# 1-Schematic_Payload_Controller.net
KiCad netlist of a schematic drawn in EasyEDA
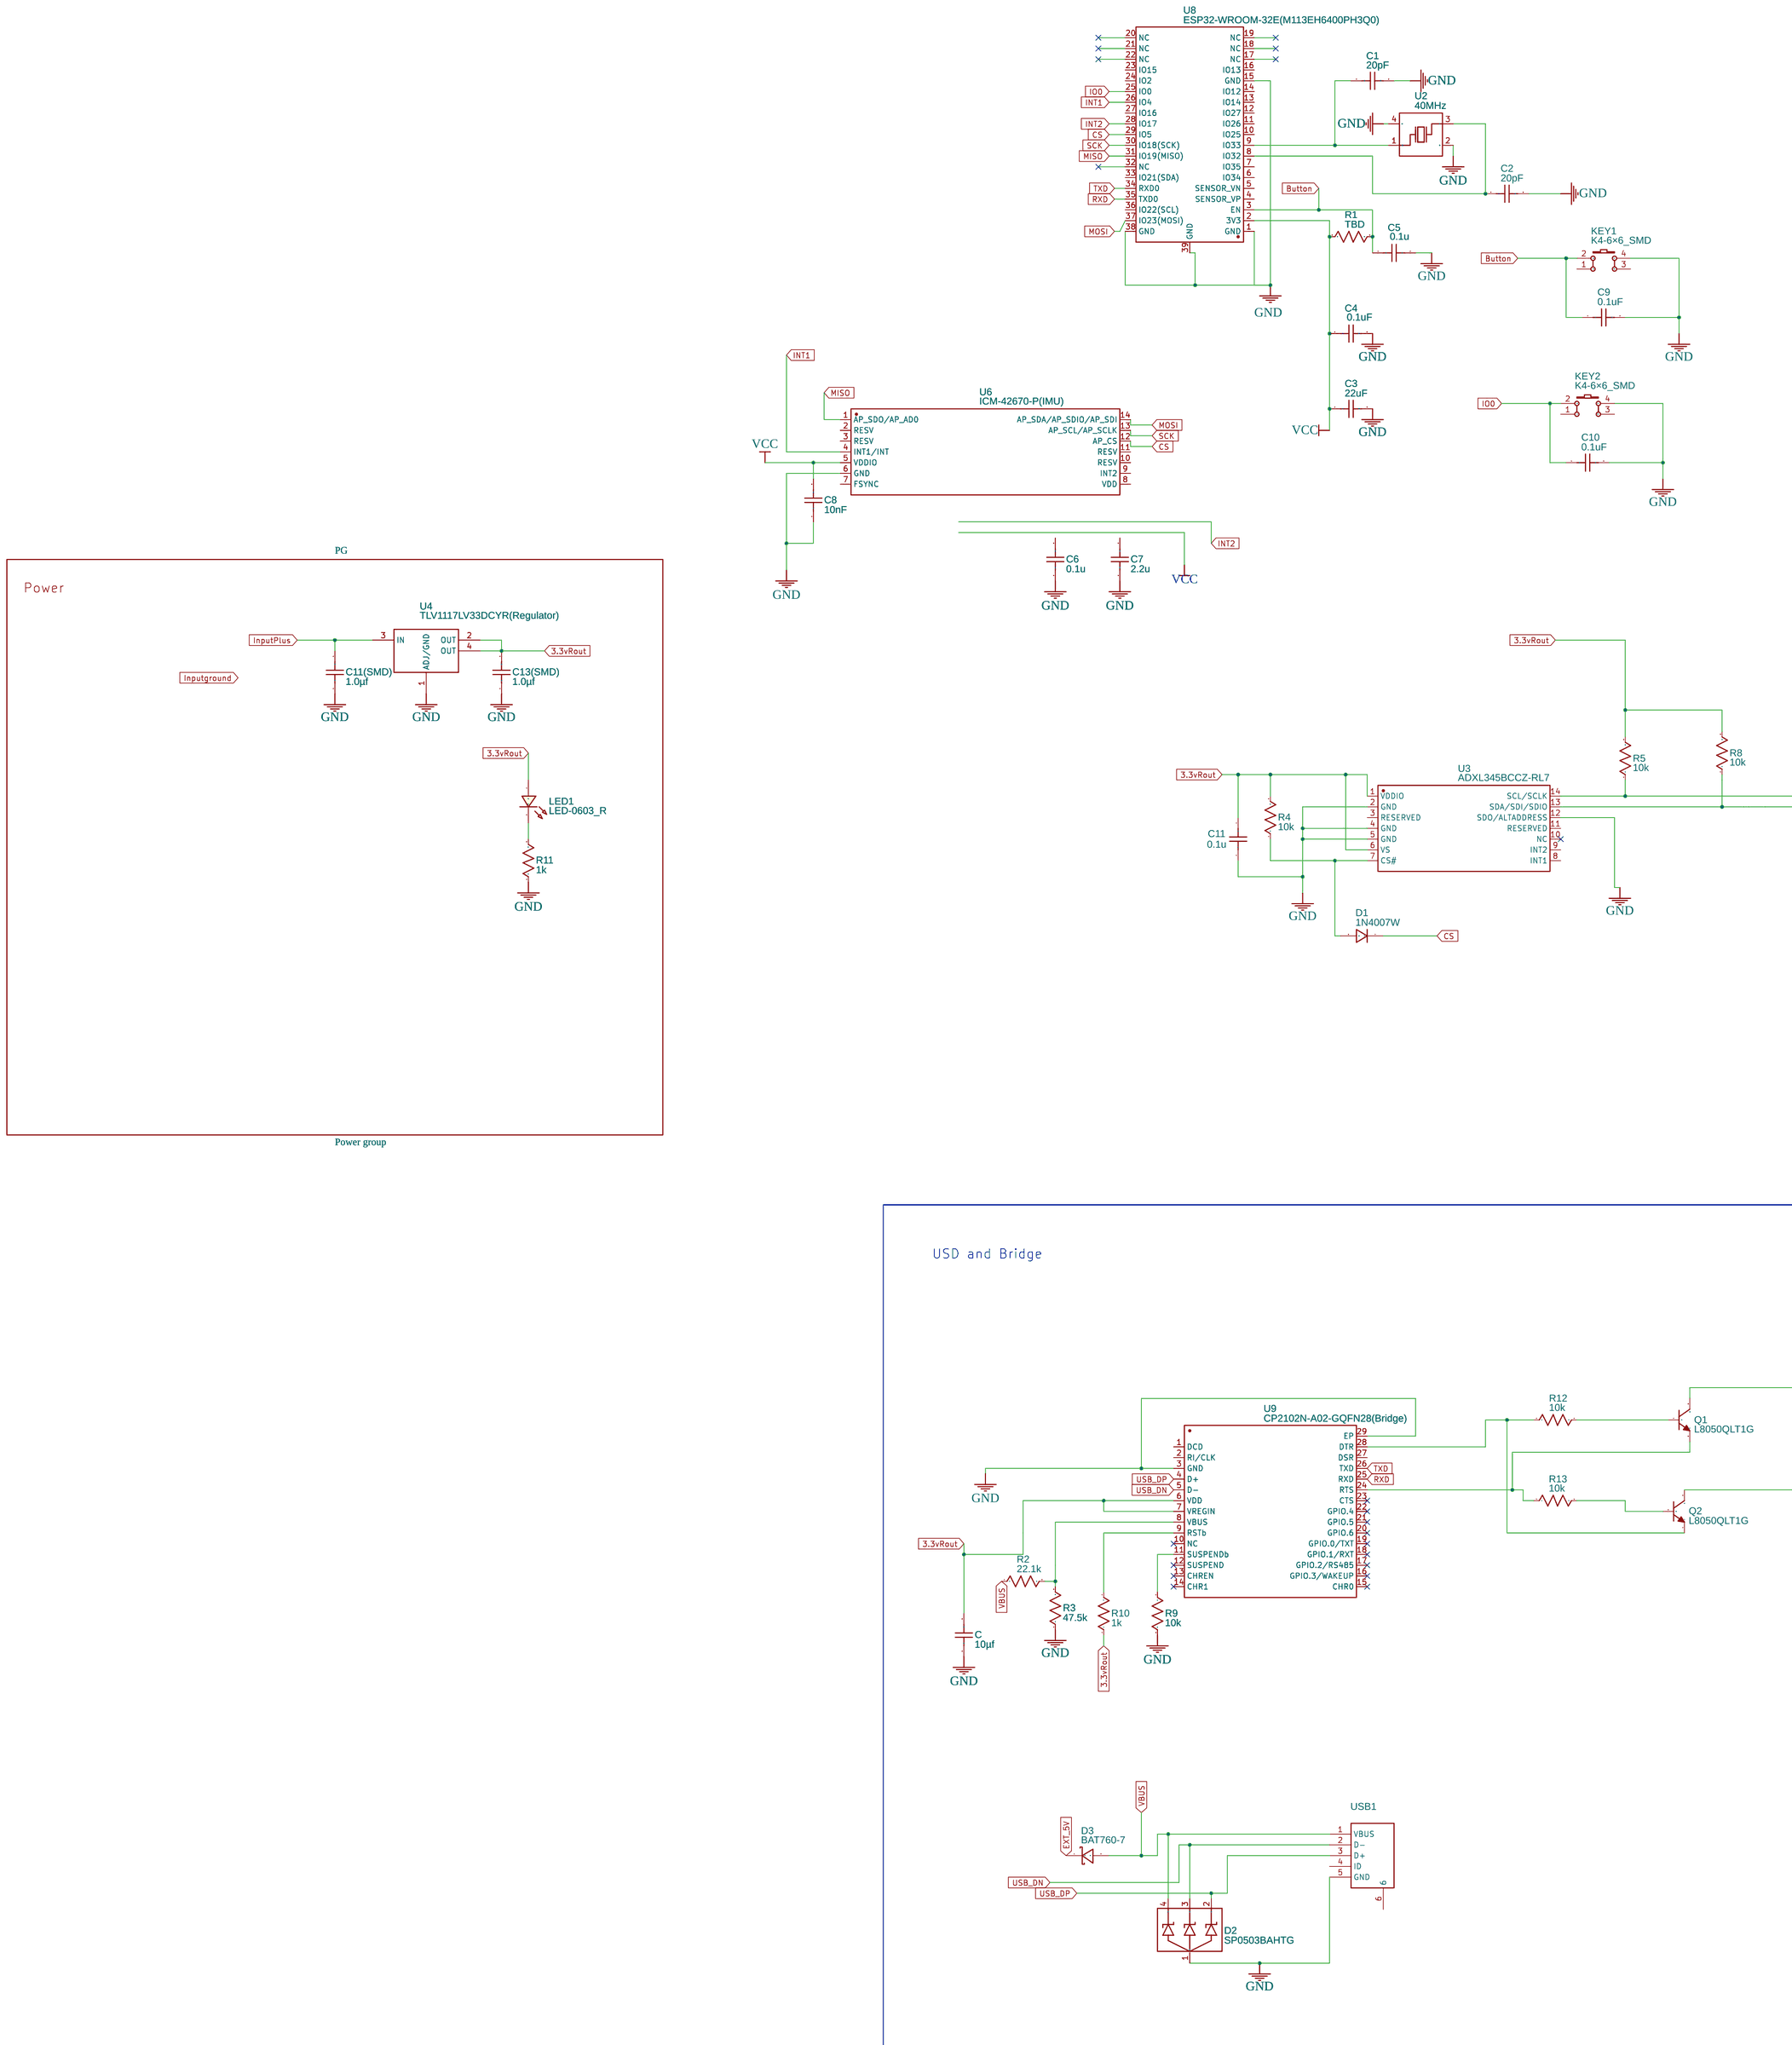
[diagram p0: schematic sheet]

(export (version "E")
  (design (tool "Eeschema 10.0.6"))
  (components
    (comp (ref "C")
      (value "10µf")
      (fields (field (name "Manufacturer Part") "100uF/25V-CAP_1206"))
      (libsource (lib "") (part "100UF/25V-CAP_1206_1"))
    )
    (comp (ref "C1") (value "20pF") (libsource (lib "") (part "C_0603_US_1")))
    (comp (ref "C2") (value "20pF") (libsource (lib "") (part "C_0603_US_1")))
    (comp (ref "C3") (value "22uF") (libsource (lib "") (part "C_0603_US_1")))
    (comp (ref "C4") (value "0.1uF") (libsource (lib "") (part "C_0603_US_1")))
    (comp (ref "C5") (value "0.1u") (libsource (lib "") (part "C_0603_US_1")))
    (comp (ref "C6") (value "0.1u") (libsource (lib "") (part "C_0603_US")))
    (comp (ref "C7") (value "2.2u") (libsource (lib "") (part "C_0603_US")))
    (comp (ref "C8") (value "10nF") (libsource (lib "") (part "C_0603_US")))
    (comp (ref "C9") (value "0.1uF") (libsource (lib "") (part "C_0603_US_1")))
    (comp (ref "C10") (value "0.1uF") (libsource (lib "") (part "C_0603_US_1")))
    (comp (ref "C11") (value "0.1u") (libsource (lib "") (part "C_0603_US_2")))
    (comp (ref "C11(SMD)")
      (value "1.0µf")
      (fields (field (name "Manufacturer Part") "100uF/25V-CAP_1206"))
      (libsource (lib "") (part "100UF/25V-CAP_1206_2"))
    )
    (comp (ref "C13(SMD)")
      (value "1.0µf")
      (fields (field (name "Manufacturer Part") "100uF/25V-CAP_1206"))
      (libsource (lib "") (part "100UF/25V-CAP_1206"))
    )
    (comp (ref "D1")
      (value "1N4007W")
      (fields (field (name "Manufacturer") "BLUE ROCKET"))
      (libsource (lib "") (part "1N4007W"))
    )
    (comp (ref "D2") (value "SP0503BAHTG") (libsource (lib "") (part "SP0503BAHTG")))
    (comp (ref "D3")
      (value "BAT760-7")
      (fields (field (name "Manufacturer") "DIODES(美台)"))
      (libsource (lib "") (part "BAT760-7"))
    )
    (comp (ref "KEY1")
      (value "K4-6×6_SMD")
      (fields (field (name "Manufacturer Part") "K2-6639SP-D4SC-04") (field (name "Manufacturer") "韩国韩荣"))
      (libsource (lib "") (part "K4-6×6_SMD"))
    )
    (comp (ref "KEY2")
      (value "K4-6×6_SMD")
      (fields (field (name "Manufacturer Part") "K2-6639SP-D4SC-04") (field (name "Manufacturer") "韩国韩荣"))
      (libsource (lib "") (part "K4-6×6_SMD"))
    )
    (comp (ref "LED1")
      (value "LED-0603_R")
      (fields
        (field (name "Manufacturer Part") "19-217/R6C-AL1M2VY/3T")
        (field (name "Manufacturer") "EVERLIGHT(台湾亿光)")
      )
      (libsource (lib "") (part "LED-0603_R"))
    )
    (comp (ref "PG") (value "Power group") (libsource (lib "") (part "Unknown_235_-290")))
    (comp (ref "Q1")
      (value "L8050QLT1G")
      (fields (field (name "Manufacturer") "LRC(乐山无线电)"))
      (libsource (lib "") (part "L8050QLT1G"))
    )
    (comp (ref "Q2")
      (value "L8050QLT1G")
      (fields (field (name "Manufacturer") "LRC(乐山无线电)"))
      (libsource (lib "") (part "L8050QLT1G"))
    )
    (comp (ref "R1") (value "TBD") (libsource (lib "") (part "R_0603_US")))
    (comp (ref "R2") (value "22.1k") (libsource (lib "") (part "R_1206_US_1")))
    (comp (ref "R3") (value "47.5k") (libsource (lib "") (part "R_1206_US")))
    (comp (ref "R4") (value "10k") (libsource (lib "") (part "R_1206_US")))
    (comp (ref "R5") (value "10k") (libsource (lib "") (part "R_1206_US")))
    (comp (ref "R8") (value "10k") (libsource (lib "") (part "R_1206_US")))
    (comp (ref "R9") (value "10k") (libsource (lib "") (part "R_1206_US_2")))
    (comp (ref "R10") (value "1k") (libsource (lib "") (part "R_1206_US")))
    (comp (ref "R11") (value "1k") (libsource (lib "") (part "R_1206_US")))
    (comp (ref "R12") (value "10k") (libsource (lib "") (part "R_1206_US_1")))
    (comp (ref "R13") (value "10k") (libsource (lib "") (part "R_1206_US_1")))
    (comp (ref "U2")
      (value "40MHz")
      (fields (field (name "Manufacturer Part") "ECS-400-10-36-CKY-TR") (field (name "Manufacturer") "ECS"))
      (libsource (lib "") (part "ECS-400-10-36-CKY-TR"))
    )
    (comp (ref "U3")
      (value "ADXL345BCCZ-RL7")
      (fields (field (name "Manufacturer") "ADI(亚德诺)"))
      (libsource (lib "") (part "ADXL345BCCZ-RL7"))
    )
    (comp (ref "U4")
      (value "TLV1117LV33DCYR(Regulator)")
      (fields (field (name "Manufacturer Part") "TLV1117LV33DCYR") (field (name "Manufacturer") "TI(德州仪器)"))
      (libsource (lib "") (part "TLV1117LV33DCYR"))
    )
    (comp (ref "U6")
      (value "ICM-42670-P(IMU)")
      (fields
        (field (name "Manufacturer Part") "ICM-42670-P")
        (field (name "Manufacturer") "TDK InvenSense(应美盛)")
      )
      (libsource (lib "") (part "ICM-42670-P"))
    )
    (comp (ref "U8")
      (value "ESP32-WROOM-32E(M113EH6400PH3Q0)")
      (fields (field (name "Manufacturer") "ESPRESSIF(乐鑫)"))
      (libsource (lib "") (part "ESP32-WROOM-32E(M113EH6400PH3Q0)"))
    )
    (comp (ref "U9")
      (value "CP2102N-A02-GQFN28(Bridge)")
      (fields
        (field (name "Manufacturer Part") "CP2102N-A02-GQFN28")
        (field (name "Manufacturer") "SKYWORKS/SILICON LABS(芯科)")
      )
      (libsource (lib "") (part "CP2102N-A02-GQFN28"))
    )
    (comp (ref "USB1")
      (value "MICRO5.9MMUSB")
      (fields (field (name "Manufacturer Part") "MICRO5.9mmusb") (field (name "Manufacturer") "SHOU HAN(首韩)"))
      (libsource (lib "") (part "MICRO5.9MMUSB"))
    )
  )
  (nets
    (net (code "1") (name "3.3vRout") (class "Default")
      (node (ref "C") (pin "2") (pinfunction "2_2") (pintype "unspecified"))
      (node (ref "C11") (pin "1") (pinfunction "1_1") (pintype "unspecified"))
      (node (ref "C13(SMD)") (pin "2") (pinfunction "2_2") (pintype "unspecified"))
      (node (ref "LED1") (pin "1") (pinfunction "1_1") (pintype "unspecified"))
      (node (ref "R10") (pin "1") (pinfunction "1_1") (pintype "unspecified"))
      (node (ref "R4") (pin "2") (pinfunction "2_2") (pintype "unspecified"))
      (node (ref "R5") (pin "2") (pinfunction "2_2") (pintype "unspecified"))
      (node (ref "R8") (pin "2") (pinfunction "2_2") (pintype "unspecified"))
      (node (ref "U3") (pin "1") (pinfunction "VDDIO_1") (pintype "unspecified"))
      (node (ref "U3") (pin "6") (pinfunction "VS_6") (pintype "unspecified"))
      (node (ref "U4") (pin "2") (pinfunction "OUT_2") (pintype "passive"))
      (node (ref "U4") (pin "4") (pinfunction "OUT_4") (pintype "passive"))
      (node (ref "U9") (pin "6") (pinfunction "VDD_6") (pintype "unspecified"))
      (node (ref "U9") (pin "7") (pinfunction "VREGIN_7") (pintype "unspecified"))
    )
    (net (code "2") (name "Button") (class "Default")
      (node (ref "C5") (pin "1") (pinfunction "1_1") (pintype "unspecified"))
      (node (ref "C9") (pin "1") (pinfunction "1_1") (pintype "unspecified"))
      (node (ref "KEY1") (pin "2") (pinfunction "2_2") (pintype "unspecified"))
      (node (ref "R1") (pin "2") (pinfunction "2_2") (pintype "unspecified"))
      (node (ref "U8") (pin "3") (pinfunction "EN_3") (pintype "unspecified"))
    )
    (net (code "3") (name "CS") (class "Default")
      (node (ref "D1") (pin "1") (pinfunction "1_1") (pintype "unspecified"))
      (node (ref "U6") (pin "12") (pinfunction "AP_CS_12") (pintype "unspecified"))
      (node (ref "U8") (pin "29") (pinfunction "IO5_29") (pintype "unspecified"))
    )
    (net (code "4") (name "ESP_RST") (class "Default")
      (node (ref "Q1") (pin "3") (pinfunction "C_3") (pintype "unspecified"))
    )
    (net (code "5") (name "EXT_5V") (class "Default")
      (node (ref "D3") (pin "1") (pinfunction "1_1") (pintype "unspecified"))
    )
    (net (code "6") (name "GND") (class "Default")
      (node (ref "C") (pin "1") (pinfunction "1_1") (pintype "unspecified"))
      (node (ref "C1") (pin "2") (pinfunction "2_2") (pintype "unspecified"))
      (node (ref "C10") (pin "2") (pinfunction "2_2") (pintype "unspecified"))
      (node (ref "C11") (pin "2") (pinfunction "2_2") (pintype "unspecified"))
      (node (ref "C11(SMD)") (pin "1") (pinfunction "1_1") (pintype "unspecified"))
      (node (ref "C13(SMD)") (pin "1") (pinfunction "1_1") (pintype "unspecified"))
      (node (ref "C2") (pin "2") (pinfunction "2_2") (pintype "unspecified"))
      (node (ref "C3") (pin "2") (pinfunction "2_2") (pintype "unspecified"))
      (node (ref "C4") (pin "2") (pinfunction "2_2") (pintype "unspecified"))
      (node (ref "C5") (pin "2") (pinfunction "2_2") (pintype "unspecified"))
      (node (ref "C6") (pin "1") (pinfunction "1_1") (pintype "unspecified"))
      (node (ref "C7") (pin "1") (pinfunction "1_1") (pintype "unspecified"))
      (node (ref "C8") (pin "1") (pinfunction "1_1") (pintype "unspecified"))
      (node (ref "C9") (pin "2") (pinfunction "2_2") (pintype "unspecified"))
      (node (ref "D2") (pin "1") (pinfunction "COMMON_1") (pintype "bidirectional"))
      (node (ref "KEY1") (pin "4") (pinfunction "4_4") (pintype "unspecified"))
      (node (ref "KEY2") (pin "4") (pinfunction "4_4") (pintype "unspecified"))
      (node (ref "R11") (pin "1") (pinfunction "1_1") (pintype "unspecified"))
      (node (ref "R3") (pin "1") (pinfunction "1_1") (pintype "unspecified"))
      (node (ref "R9") (pin "2") (pinfunction "2_2") (pintype "unspecified"))
      (node (ref "U2") (pin "2") (pinfunction "Gnd_2") (pintype "unspecified"))
      (node (ref "U2") (pin "4") (pinfunction "Gnd_4") (pintype "unspecified"))
      (node (ref "U3") (pin "12") (pinfunction "SDO/ALTADDRESS_12") (pintype "unspecified"))
      (node (ref "U3") (pin "2") (pinfunction "GND_2") (pintype "unspecified"))
      (node (ref "U3") (pin "4") (pinfunction "GND_4") (pintype "unspecified"))
      (node (ref "U3") (pin "5") (pinfunction "GND_5") (pintype "unspecified"))
      (node (ref "U4") (pin "1") (pinfunction "ADJ/GND_1") (pintype "passive"))
      (node (ref "U6") (pin "6") (pinfunction "GND_6") (pintype "unspecified"))
      (node (ref "U8") (pin "1") (pinfunction "GND_1") (pintype "unspecified"))
      (node (ref "U8") (pin "15") (pinfunction "GND_15") (pintype "unspecified"))
      (node (ref "U8") (pin "38") (pinfunction "GND_38") (pintype "unspecified"))
      (node (ref "U8") (pin "39") (pinfunction "GND_39") (pintype "unspecified"))
      (node (ref "U9") (pin "29") (pinfunction "EP_29") (pintype "unspecified"))
      (node (ref "U9") (pin "3") (pinfunction "GND_3") (pintype "unspecified"))
      (node (ref "USB1") (pin "5") (pinfunction "GND_5") (pintype "unspecified"))
    )
    (net (code "7") (name "INT1") (class "Default")
      (node (ref "U6") (pin "4") (pinfunction "INT1/INT_4") (pintype "unspecified"))
      (node (ref "U8") (pin "26") (pinfunction "IO4_26") (pintype "unspecified"))
    )
    (net (code "8") (name "INT2") (class "Default")
      (node (ref "U8") (pin "28") (pinfunction "IO17_28") (pintype "unspecified"))
    )
    (net (code "9") (name "IO0") (class "Default")
      (node (ref "C10") (pin "1") (pinfunction "1_1") (pintype "unspecified"))
      (node (ref "KEY2") (pin "2") (pinfunction "2_2") (pintype "unspecified"))
      (node (ref "Q2") (pin "3") (pinfunction "C_3") (pintype "unspecified"))
      (node (ref "U8") (pin "25") (pinfunction "IO0_25") (pintype "unspecified"))
    )
    (net (code "10") (name "InputPlus") (class "Default")
      (node (ref "C11(SMD)") (pin "2") (pinfunction "2_2") (pintype "unspecified"))
      (node (ref "U4") (pin "3") (pinfunction "IN_3") (pintype "passive"))
    )
    (net (code "12") (name "MISO") (class "Default")
      (node (ref "U6") (pin "1") (pinfunction "AP_SDO/AP_AD0_1") (pintype "unspecified"))
      (node (ref "U8") (pin "31") (pinfunction "IO19(MISO)_31") (pintype "unspecified"))
    )
    (net (code "13") (name "MOSI") (class "Default")
      (node (ref "U6") (pin "14") (pinfunction "AP_SDA/AP_SDIO/AP_SDI_14") (pintype "unspecified"))
      (node (ref "U8") (pin "37") (pinfunction "IO23(MOSI)_37") (pintype "unspecified"))
    )
    (net (code "14") (name "Net-(LED1-Pad2)") (class "Default")
      (node (ref "LED1") (pin "2") (pinfunction "2_2") (pintype "unspecified"))
      (node (ref "R11") (pin "2") (pinfunction "2_2") (pintype "unspecified"))
    )
    (net (code "15") (name "Net-(Q1-B)") (class "Default")
      (node (ref "Q1") (pin "1") (pinfunction "B_1") (pintype "unspecified"))
      (node (ref "R12") (pin "2") (pinfunction "2_2") (pintype "unspecified"))
    )
    (net (code "16") (name "Net-(Q1-E)") (class "Default")
      (node (ref "Q1") (pin "2") (pinfunction "E_2") (pintype "unspecified"))
      (node (ref "R13") (pin "1") (pinfunction "1_1") (pintype "unspecified"))
      (node (ref "U9") (pin "24") (pinfunction "RTS_24") (pintype "unspecified"))
    )
    (net (code "17") (name "Net-(Q2-B)") (class "Default")
      (node (ref "Q2") (pin "1") (pinfunction "B_1") (pintype "unspecified"))
      (node (ref "R13") (pin "2") (pinfunction "2_2") (pintype "unspecified"))
    )
    (net (code "18") (name "Net-(Q2-E)") (class "Default")
      (node (ref "Q2") (pin "2") (pinfunction "E_2") (pintype "unspecified"))
      (node (ref "R12") (pin "1") (pinfunction "1_1") (pintype "unspecified"))
      (node (ref "U9") (pin "28") (pinfunction "DTR_28") (pintype "unspecified"))
    )
    (net (code "19") (name "Net-(U2-In{slash}Out)") (class "Default")
      (node (ref "C1") (pin "1") (pinfunction "1_1") (pintype "unspecified"))
      (node (ref "U2") (pin "1") (pinfunction "In/Out_1") (pintype "unspecified"))
      (node (ref "U8") (pin "9") (pinfunction "IO33_9") (pintype "unspecified"))
    )
    (net (code "20") (name "Net-(U2-Out{slash}In)") (class "Default")
      (node (ref "C2") (pin "1") (pinfunction "1_1") (pintype "unspecified"))
      (node (ref "U2") (pin "3") (pinfunction "Out/In_3") (pintype "unspecified"))
      (node (ref "U8") (pin "8") (pinfunction "IO32_8") (pintype "unspecified"))
    )
    (net (code "21") (name "Net-(U3-CS#)") (class "Default")
      (node (ref "D1") (pin "2") (pinfunction "2_2") (pintype "unspecified"))
      (node (ref "R4") (pin "1") (pinfunction "1_1") (pintype "unspecified"))
      (node (ref "U3") (pin "7") (pinfunction "CS#_7") (pintype "unspecified"))
    )
    (net (code "22") (name "Net-(U9-RSTb)") (class "Default")
      (node (ref "R10") (pin "2") (pinfunction "2_2") (pintype "unspecified"))
      (node (ref "U9") (pin "9") (pinfunction "RSTb_9") (pintype "unspecified"))
    )
    (net (code "23") (name "Net-(U9-SUSPENDb)") (class "Default")
      (node (ref "R9") (pin "1") (pinfunction "1_1") (pintype "unspecified"))
      (node (ref "U9") (pin "11") (pinfunction "SUSPENDb_11") (pintype "unspecified"))
    )
    (net (code "24") (name "Net-(U9-VBUS)") (class "Default")
      (node (ref "R2") (pin "2") (pinfunction "2_2") (pintype "unspecified"))
      (node (ref "R3") (pin "2") (pinfunction "2_2") (pintype "unspecified"))
      (node (ref "U9") (pin "8") (pinfunction "VBUS_8") (pintype "unspecified"))
    )
    (net (code "25") (name "RXD") (class "Default")
      (node (ref "U8") (pin "35") (pinfunction "TXD0_35") (pintype "unspecified"))
      (node (ref "U9") (pin "25") (pinfunction "RXD_25") (pintype "unspecified"))
    )
    (net (code "26") (name "SCK") (class "Default")
      (node (ref "U6") (pin "13") (pinfunction "AP_SCL/AP_SCLK_13") (pintype "unspecified"))
      (node (ref "U8") (pin "30") (pinfunction "IO18(SCK)_30") (pintype "unspecified"))
    )
    (net (code "27") (name "SCL") (class "Default")
      (node (ref "R8") (pin "1") (pinfunction "1_1") (pintype "unspecified"))
      (node (ref "U3") (pin "13") (pinfunction "SDA/SDI/SDIO_13") (pintype "unspecified"))
    )
    (net (code "28") (name "SDA") (class "Default")
      (node (ref "R5") (pin "1") (pinfunction "1_1") (pintype "unspecified"))
      (node (ref "U3") (pin "14") (pinfunction "SCL/SCLK_14") (pintype "unspecified"))
    )
    (net (code "29") (name "TXD") (class "Default")
      (node (ref "U8") (pin "34") (pinfunction "RXD0_34") (pintype "unspecified"))
      (node (ref "U9") (pin "26") (pinfunction "TXD_26") (pintype "unspecified"))
    )
    (net (code "30") (name "USB_DN") (class "Default")
      (node (ref "D2") (pin "3") (pinfunction "K2_3") (pintype "bidirectional"))
      (node (ref "U9") (pin "5") (pinfunction "D-_5") (pintype "unspecified"))
      (node (ref "USB1") (pin "2") (pinfunction "D-_2") (pintype "unspecified"))
    )
    (net (code "31") (name "USB_DP") (class "Default")
      (node (ref "D2") (pin "2") (pinfunction "K3_2") (pintype "bidirectional"))
      (node (ref "U9") (pin "4") (pinfunction "D+_4") (pintype "unspecified"))
      (node (ref "USB1") (pin "3") (pinfunction "D+_3") (pintype "unspecified"))
    )
    (net (code "32") (name "VBUS") (class "Default")
      (node (ref "D2") (pin "4") (pinfunction "K1_4") (pintype "bidirectional"))
      (node (ref "D3") (pin "2") (pinfunction "2_2") (pintype "unspecified"))
      (node (ref "R2") (pin "1") (pinfunction "1_1") (pintype "unspecified"))
      (node (ref "USB1") (pin "1") (pinfunction "VBUS_1") (pintype "unspecified"))
    )
    (net (code "33") (name "VCC") (class "Default")
      (node (ref "C3") (pin "1") (pinfunction "1_1") (pintype "unspecified"))
      (node (ref "C4") (pin "1") (pinfunction "1_1") (pintype "unspecified"))
      (node (ref "C8") (pin "2") (pinfunction "2_2") (pintype "unspecified"))
      (node (ref "R1") (pin "1") (pinfunction "1_1") (pintype "unspecified"))
      (node (ref "U6") (pin "5") (pinfunction "VDDIO_5") (pintype "unspecified"))
      (node (ref "U8") (pin "2") (pinfunction "3V3_2") (pintype "unspecified"))
    )
    (net (code "34") (name "unconnected-(C6-Pad2)") (class "Default")
      (node (ref "C6") (pin "2") (pinfunction "2_2") (pintype "unspecified"))
    )
    (net (code "35") (name "unconnected-(C7-Pad2)") (class "Default")
      (node (ref "C7") (pin "2") (pinfunction "2_2") (pintype "unspecified"))
    )
    (net (code "36") (name "unconnected-(KEY1-Pad1)") (class "Default")
      (node (ref "KEY1") (pin "1") (pinfunction "1_1") (pintype "unspecified"))
    )
    (net (code "37") (name "unconnected-(KEY1-Pad3)") (class "Default")
      (node (ref "KEY1") (pin "3") (pinfunction "3_3") (pintype "unspecified"))
    )
    (net (code "38") (name "unconnected-(KEY2-Pad1)") (class "Default")
      (node (ref "KEY2") (pin "1") (pinfunction "1_1") (pintype "unspecified"))
    )
    (net (code "39") (name "unconnected-(KEY2-Pad3)") (class "Default")
      (node (ref "KEY2") (pin "3") (pinfunction "3_3") (pintype "unspecified"))
    )
    (net (code "40") (name "unconnected-(U3-INT1-Pad8)") (class "Default")
      (node (ref "U3") (pin "8") (pinfunction "INT1_8") (pintype "unspecified"))
    )
    (net (code "41") (name "unconnected-(U3-INT2-Pad9)") (class "Default")
      (node (ref "U3") (pin "9") (pinfunction "INT2_9") (pintype "unspecified"))
    )
    (net (code "42") (name "unconnected-(U3-NC-Pad10)") (class "Default")
      (node (ref "U3") (pin "10") (pinfunction "NC_10") (pintype "unspecified+no_connect"))
    )
    (net (code "43") (name "unconnected-(U3-RESERVED-Pad3)") (class "Default")
      (node (ref "U3") (pin "3") (pinfunction "RESERVED_3") (pintype "unspecified"))
    )
    (net (code "44") (name "unconnected-(U3-RESERVED-Pad11)") (class "Default")
      (node (ref "U3") (pin "11") (pinfunction "RESERVED_11") (pintype "unspecified"))
    )
    (net (code "45") (name "unconnected-(U6-FSYNC-Pad7)") (class "Default")
      (node (ref "U6") (pin "7") (pinfunction "FSYNC_7") (pintype "unspecified"))
    )
    (net (code "46") (name "unconnected-(U6-INT2-Pad9)") (class "Default")
      (node (ref "U6") (pin "9") (pinfunction "INT2_9") (pintype "unspecified"))
    )
    (net (code "47") (name "unconnected-(U6-RESV-Pad2)") (class "Default")
      (node (ref "U6") (pin "2") (pinfunction "RESV_2") (pintype "unspecified"))
    )
    (net (code "48") (name "unconnected-(U6-RESV-Pad3)") (class "Default")
      (node (ref "U6") (pin "3") (pinfunction "RESV_3") (pintype "unspecified"))
    )
    (net (code "49") (name "unconnected-(U6-RESV-Pad10)") (class "Default")
      (node (ref "U6") (pin "10") (pinfunction "RESV_10") (pintype "unspecified"))
    )
    (net (code "50") (name "unconnected-(U6-RESV-Pad11)") (class "Default")
      (node (ref "U6") (pin "11") (pinfunction "RESV_11") (pintype "unspecified"))
    )
    (net (code "51") (name "unconnected-(U6-VDD-Pad8)") (class "Default")
      (node (ref "U6") (pin "8") (pinfunction "VDD_8") (pintype "unspecified"))
    )
    (net (code "52") (name "unconnected-(U8-IO2-Pad24)") (class "Default")
      (node (ref "U8") (pin "24") (pinfunction "IO2_24") (pintype "unspecified"))
    )
    (net (code "53") (name "unconnected-(U8-IO12-Pad14)") (class "Default")
      (node (ref "U8") (pin "14") (pinfunction "IO12_14") (pintype "unspecified"))
    )
    (net (code "54") (name "unconnected-(U8-IO13-Pad16)") (class "Default")
      (node (ref "U8") (pin "16") (pinfunction "IO13_16") (pintype "unspecified"))
    )
    (net (code "55") (name "unconnected-(U8-IO14-Pad13)") (class "Default")
      (node (ref "U8") (pin "13") (pinfunction "IO14_13") (pintype "unspecified"))
    )
    (net (code "56") (name "unconnected-(U8-IO15-Pad23)") (class "Default")
      (node (ref "U8") (pin "23") (pinfunction "IO15_23") (pintype "unspecified"))
    )
    (net (code "57") (name "unconnected-(U8-IO16-Pad27)") (class "Default")
      (node (ref "U8") (pin "27") (pinfunction "IO16_27") (pintype "unspecified"))
    )
    (net (code "58") (name "unconnected-(U8-IO21(SDA)-Pad33)") (class "Default")
      (node (ref "U8") (pin "33") (pinfunction "IO21(SDA)_33") (pintype "unspecified"))
    )
    (net (code "59") (name "unconnected-(U8-IO22(SCL)-Pad36)") (class "Default")
      (node (ref "U8") (pin "36") (pinfunction "IO22(SCL)_36") (pintype "unspecified"))
    )
    (net (code "60") (name "unconnected-(U8-IO25-Pad10)") (class "Default")
      (node (ref "U8") (pin "10") (pinfunction "IO25_10") (pintype "unspecified"))
    )
    (net (code "61") (name "unconnected-(U8-IO26-Pad11)") (class "Default")
      (node (ref "U8") (pin "11") (pinfunction "IO26_11") (pintype "unspecified"))
    )
    (net (code "62") (name "unconnected-(U8-IO27-Pad12)") (class "Default")
      (node (ref "U8") (pin "12") (pinfunction "IO27_12") (pintype "unspecified"))
    )
    (net (code "63") (name "unconnected-(U8-IO34-Pad6)") (class "Default")
      (node (ref "U8") (pin "6") (pinfunction "IO34_6") (pintype "unspecified"))
    )
    (net (code "64") (name "unconnected-(U8-IO35-Pad7)") (class "Default")
      (node (ref "U8") (pin "7") (pinfunction "IO35_7") (pintype "unspecified"))
    )
    (net (code "65") (name "unconnected-(U8-NC-Pad17)") (class "Default")
      (node (ref "U8") (pin "17") (pinfunction "NC_17") (pintype "unspecified+no_connect"))
    )
    (net (code "66") (name "unconnected-(U8-NC-Pad18)") (class "Default")
      (node (ref "U8") (pin "18") (pinfunction "NC_18") (pintype "unspecified+no_connect"))
    )
    (net (code "67") (name "unconnected-(U8-NC-Pad19)") (class "Default")
      (node (ref "U8") (pin "19") (pinfunction "NC_19") (pintype "unspecified+no_connect"))
    )
    (net (code "68") (name "unconnected-(U8-NC-Pad20)") (class "Default")
      (node (ref "U8") (pin "20") (pinfunction "NC_20") (pintype "unspecified+no_connect"))
    )
    (net (code "69") (name "unconnected-(U8-NC-Pad21)") (class "Default")
      (node (ref "U8") (pin "21") (pinfunction "NC_21") (pintype "unspecified+no_connect"))
    )
    (net (code "70") (name "unconnected-(U8-NC-Pad22)") (class "Default")
      (node (ref "U8") (pin "22") (pinfunction "NC_22") (pintype "unspecified+no_connect"))
    )
    (net (code "71") (name "unconnected-(U8-NC-Pad32)") (class "Default")
      (node (ref "U8") (pin "32") (pinfunction "NC_32") (pintype "unspecified+no_connect"))
    )
    (net (code "72") (name "unconnected-(U8-SENSOR_VN-Pad5)") (class "Default")
      (node (ref "U8") (pin "5") (pinfunction "SENSOR_VN_5") (pintype "unspecified"))
    )
    (net (code "73") (name "unconnected-(U8-SENSOR_VP-Pad4)") (class "Default")
      (node (ref "U8") (pin "4") (pinfunction "SENSOR_VP_4") (pintype "unspecified"))
    )
    (net (code "74") (name "unconnected-(U9-CHR0-Pad15)") (class "Default")
      (node (ref "U9") (pin "15") (pinfunction "CHR0_15") (pintype "unspecified+no_connect"))
    )
    (net (code "75") (name "unconnected-(U9-CHR1-Pad14)") (class "Default")
      (node (ref "U9") (pin "14") (pinfunction "CHR1_14") (pintype "unspecified+no_connect"))
    )
    (net (code "76") (name "unconnected-(U9-CHREN-Pad13)") (class "Default")
      (node (ref "U9") (pin "13") (pinfunction "CHREN_13") (pintype "unspecified+no_connect"))
    )
    (net (code "77") (name "unconnected-(U9-CTS-Pad23)") (class "Default")
      (node (ref "U9") (pin "23") (pinfunction "CTS_23") (pintype "unspecified+no_connect"))
    )
    (net (code "78") (name "unconnected-(U9-DCD-Pad1)") (class "Default")
      (node (ref "U9") (pin "1") (pinfunction "DCD_1") (pintype "unspecified"))
    )
    (net (code "79") (name "unconnected-(U9-DSR-Pad27)") (class "Default")
      (node (ref "U9") (pin "27") (pinfunction "DSR_27") (pintype "unspecified"))
    )
    (net (code "80") (name "unconnected-(U9-GPIO.0{slash}TXT-Pad19)") (class "Default")
      (node (ref "U9") (pin "19") (pinfunction "GPIO.0/TXT_19") (pintype "unspecified+no_connect"))
    )
    (net (code "81") (name "unconnected-(U9-GPIO.1{slash}RXT-Pad18)") (class "Default")
      (node (ref "U9") (pin "18") (pinfunction "GPIO.1/RXT_18") (pintype "unspecified+no_connect"))
    )
    (net (code "82") (name "unconnected-(U9-GPIO.2{slash}RS485-Pad17)") (class "Default")
      (node (ref "U9") (pin "17") (pinfunction "GPIO.2/RS485_17") (pintype "unspecified+no_connect"))
    )
    (net (code "83") (name "unconnected-(U9-GPIO.3{slash}WAKEUP-Pad16)") (class "Default")
      (node (ref "U9") (pin "16") (pinfunction "GPIO.3/WAKEUP_16") (pintype "unspecified+no_connect"))
    )
    (net (code "84") (name "unconnected-(U9-GPIO.4-Pad22)") (class "Default")
      (node (ref "U9") (pin "22") (pinfunction "GPIO.4_22") (pintype "unspecified+no_connect"))
    )
    (net (code "85") (name "unconnected-(U9-GPIO.5-Pad21)") (class "Default")
      (node (ref "U9") (pin "21") (pinfunction "GPIO.5_21") (pintype "unspecified+no_connect"))
    )
    (net (code "86") (name "unconnected-(U9-GPIO.6-Pad20)") (class "Default")
      (node (ref "U9") (pin "20") (pinfunction "GPIO.6_20") (pintype "unspecified+no_connect"))
    )
    (net (code "87") (name "unconnected-(U9-NC-Pad10)") (class "Default")
      (node (ref "U9") (pin "10") (pinfunction "NC_10") (pintype "unspecified+no_connect"))
    )
    (net (code "88") (name "unconnected-(U9-RI{slash}CLK-Pad2)") (class "Default")
      (node (ref "U9") (pin "2") (pinfunction "RI/CLK_2") (pintype "unspecified"))
    )
    (net (code "89") (name "unconnected-(U9-SUSPEND-Pad12)") (class "Default")
      (node (ref "U9") (pin "12") (pinfunction "SUSPEND_12") (pintype "unspecified+no_connect"))
    )
    (net (code "90") (name "unconnected-(USB1-ID-Pad4)") (class "Default")
      (node (ref "USB1") (pin "4") (pinfunction "ID_4") (pintype "unspecified"))
    )
    (net (code "91") (name "unconnected-(USB1-Pad6)") (class "Default")
      (node (ref "USB1") (pin "6") (pinfunction "6_6") (pintype "unspecified"))
    )
  )
)
